# core.net
KiCad netlist of a schematic drawn in Altium Designer
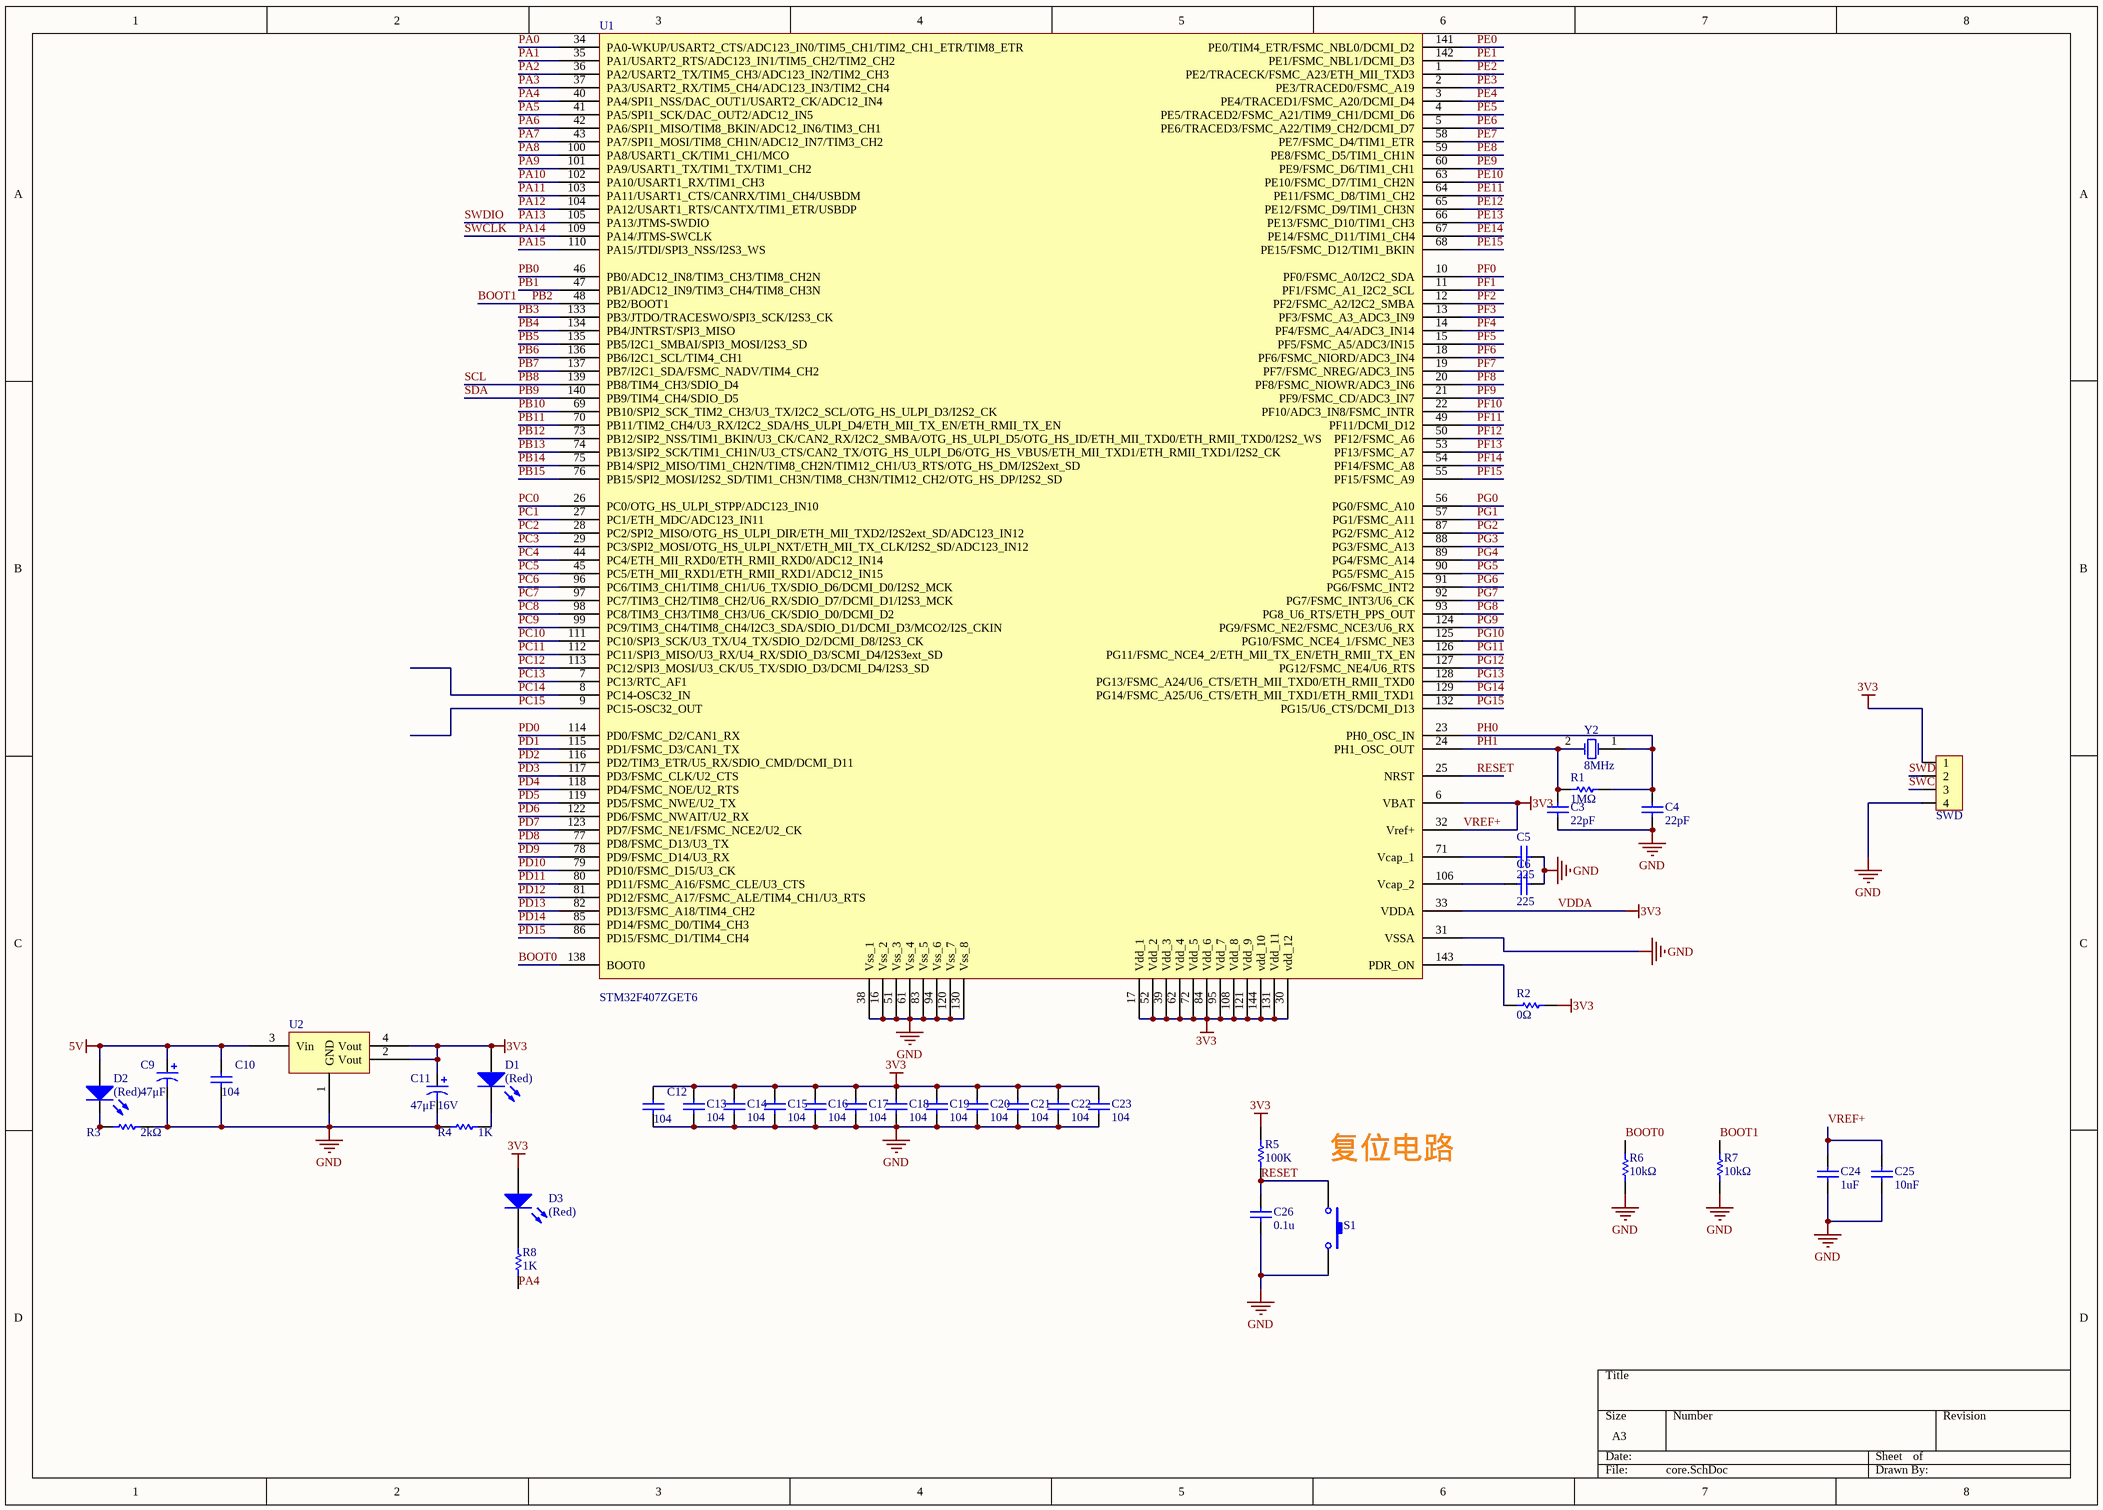
[diagram p0: core.SchDoc]

(export (version "E")
  (design (tool "Eeschema 10.0.6"))
  (components
    (comp (ref "C3")
      (value "22pF")
      (footprint "CAP-MLCC-0603")
      (description "无极性电容")
      (fields (field (name "Comment") "CAP") (field (name "PUBLISHER") "Altium Limited"))
      (libsource (lib "Libraries_2014_0215") (part "CAP"))
    )
    (comp (ref "C4")
      (value "22pF")
      (footprint "CAP-MLCC-0603")
      (description "无极性电容")
      (fields (field (name "Comment") "CAP") (field (name "PUBLISHER") "Altium Limited"))
      (libsource (lib "Libraries_2014_0215") (part "CAP"))
    )
    (comp (ref "C5")
      (value "225")
      (footprint "CAP-MLCC-0603")
      (description "无极性电容")
      (fields (field (name "PUBLISHER") "Altium Limited"))
      (libsource (lib "Libraries_2014_0618") (part "CAP"))
    )
    (comp (ref "C6")
      (value "225")
      (footprint "CAP-MLCC-0603")
      (description "无极性电容")
      (fields (field (name "PUBLISHER") "Altium Limited"))
      (libsource (lib "Libraries_2014_0618") (part "CAP"))
    )
    (comp (ref "C9")
      (value "47μF")
      (footprint "CAP-TAN-6032/CAPC")
      (description "钽电容")
      (fields (field (name "Comment") "CAP-TAN") (field (name "PUBLISHER") "Altium Limited"))
      (libsource (lib "Libraries_2014_0215") (part "CAP-TAN"))
    )
    (comp (ref "C10")
      (value "104")
      (footprint "CAP-MLCC-0603")
      (description "无极性电容")
      (fields (field (name "Comment") "CAP") (field (name "PUBLISHER") "Altium Limited"))
      (libsource (lib "Libraries_2014_0215") (part "CAP"))
    )
    (comp (ref "C11")
      (value "47μF")
      (footprint "CAP-TAN-6032/CAPC")
      (description "钽电容")
      (fields (field (name "Comment") "CAP-TAN") (field (name "PUBLISHER") "Altium Limited"))
      (libsource (lib "Libraries_2014_0215") (part "CAP-TAN"))
    )
    (comp (ref "C12")
      (value "104")
      (footprint "CAP-MLCC-0603")
      (description "无极性电容")
      (fields (field (name "Comment") "CAP") (field (name "PUBLISHER") "Altium Limited"))
      (libsource (lib "Libraries_2014_0215") (part "CAP"))
    )
    (comp (ref "C13")
      (value "104")
      (footprint "CAP-MLCC-0603")
      (description "无极性电容")
      (fields (field (name "Comment") "CAP") (field (name "PUBLISHER") "Altium Limited"))
      (libsource (lib "Libraries_2014_0215") (part "CAP"))
    )
    (comp (ref "C14")
      (value "104")
      (footprint "CAP-MLCC-0603")
      (description "无极性电容")
      (fields (field (name "Comment") "CAP") (field (name "PUBLISHER") "Altium Limited"))
      (libsource (lib "Libraries_2014_0215") (part "CAP"))
    )
    (comp (ref "C15")
      (value "104")
      (footprint "CAP-MLCC-0603")
      (description "无极性电容")
      (fields (field (name "Comment") "CAP") (field (name "PUBLISHER") "Altium Limited"))
      (libsource (lib "Libraries_2014_0215") (part "CAP"))
    )
    (comp (ref "C16")
      (value "104")
      (footprint "CAP-MLCC-0603")
      (description "无极性电容")
      (fields (field (name "Comment") "CAP") (field (name "PUBLISHER") "Altium Limited"))
      (libsource (lib "Libraries_2014_0215") (part "CAP"))
    )
    (comp (ref "C17")
      (value "104")
      (footprint "CAP-MLCC-0603")
      (description "无极性电容")
      (fields (field (name "Comment") "CAP") (field (name "PUBLISHER") "Altium Limited"))
      (libsource (lib "Libraries_2014_0215") (part "CAP"))
    )
    (comp (ref "C18")
      (value "104")
      (footprint "CAP-MLCC-0603")
      (description "无极性电容")
      (fields (field (name "Comment") "CAP") (field (name "PUBLISHER") "Altium Limited"))
      (libsource (lib "Libraries_2014_0215") (part "CAP"))
    )
    (comp (ref "C19")
      (value "104")
      (footprint "CAP-MLCC-0603")
      (description "无极性电容")
      (fields (field (name "Comment") "CAP") (field (name "PUBLISHER") "Altium Limited"))
      (libsource (lib "Libraries_2014_0215") (part "CAP"))
    )
    (comp (ref "C20")
      (value "104")
      (footprint "CAP-MLCC-0603")
      (description "无极性电容")
      (fields (field (name "Comment") "CAP") (field (name "PUBLISHER") "Altium Limited"))
      (libsource (lib "Libraries_2014_0215") (part "CAP"))
    )
    (comp (ref "C21")
      (value "104")
      (footprint "CAP-MLCC-0603")
      (description "无极性电容")
      (fields (field (name "Comment") "CAP") (field (name "PUBLISHER") "Altium Limited"))
      (libsource (lib "Libraries_2014_0215") (part "CAP"))
    )
    (comp (ref "C22")
      (value "104")
      (footprint "CAP-MLCC-0603")
      (description "无极性电容")
      (fields (field (name "Comment") "CAP") (field (name "PUBLISHER") "Altium Limited"))
      (libsource (lib "Libraries_2014_0215") (part "CAP"))
    )
    (comp (ref "C23")
      (value "104")
      (footprint "CAP-MLCC-0603")
      (description "无极性电容")
      (fields (field (name "Comment") "CAP") (field (name "PUBLISHER") "Altium Limited"))
      (libsource (lib "Libraries_2014_0215") (part "CAP"))
    )
    (comp (ref "C24")
      (value "1uF")
      (footprint "CAP-MLCC-0603")
      (description "无极性电容")
      (fields (field (name "PUBLISHER") "Altium Limited"))
      (libsource (lib "Libraries_2014_0618") (part "CAP"))
    )
    (comp (ref "C25")
      (value "10nF")
      (footprint "CAP-MLCC-0603")
      (description "无极性电容")
      (fields (field (name "PUBLISHER") "Altium Limited"))
      (libsource (lib "Libraries_2014_0618") (part "CAP"))
    )
    (comp (ref "C26")
      (value "0.1u")
      (footprint "CAP-MLCC-0603")
      (description "无极性电容")
      (fields (field (name "PUBLISHER") "Altium Limited"))
      (libsource (lib "Libraries_2014_0618") (part "CAP"))
    )
    (comp (ref "D1")
      (value "(Red)")
      (footprint "LED-1206")
      (description "LED")
      (fields (field (name "PUBLISHER") "Altium Limited"))
      (libsource (lib "Libraries_2014_0215") (part "LED"))
    )
    (comp (ref "D2")
      (value "(Red)")
      (footprint "LED-1206")
      (description "LED")
      (fields (field (name "PUBLISHER") "Altium Limited"))
      (libsource (lib "Libraries_2014_0215") (part "LED"))
    )
    (comp (ref "D3")
      (value "(Red)")
      (footprint "LED-1206")
      (description "LED")
      (fields (field (name "PUBLISHER") "Altium Limited"))
      (libsource (lib "Libraries_2014_0215") (part "LED"))
    )
    (comp (ref "R1")
      (value "1MΩ")
      (footprint "RES-0603")
      (description "电阻")
      (fields (field (name "PUBLISHER") "Altium Limited"))
      (libsource (lib "Libraries_2014_0618") (part "RES"))
    )
    (comp (ref "R2")
      (value "0Ω")
      (footprint "RES-0603")
      (description "电阻")
      (fields (field (name "PUBLISHER") "Altium Limited"))
      (libsource (lib "Libraries_2014_0618") (part "RES"))
    )
    (comp (ref "R3")
      (value "2kΩ")
      (footprint "RES-0603")
      (description "电阻")
      (fields (field (name "Comment") "RES") (field (name "PUBLISHER") "Altium Limited"))
      (libsource (lib "Libraries_2014_0215") (part "RES"))
    )
    (comp (ref "R4")
      (value "1K")
      (footprint "RES-0603")
      (description "电阻")
      (fields (field (name "Comment") "RES") (field (name "PUBLISHER") "Altium Limited"))
      (libsource (lib "Libraries_2014_0215") (part "RES"))
    )
    (comp (ref "R5")
      (value "100K")
      (footprint "RES-0603")
      (description "电阻")
      (fields (field (name "Comment") "RES") (field (name "PUBLISHER") "Altium Limited"))
      (libsource (lib "Libraries_2014_0215") (part "RES"))
    )
    (comp (ref "R6")
      (value "10kΩ")
      (footprint "RES-0603")
      (description "电阻")
      (fields (field (name "Comment") "RES") (field (name "PUBLISHER") "Altium Limited"))
      (libsource (lib "Libraries_2014_0215") (part "RES"))
    )
    (comp (ref "R7")
      (value "10kΩ")
      (footprint "RES-0603")
      (description "电阻")
      (fields (field (name "Comment") "RES") (field (name "PUBLISHER") "Altium Limited"))
      (libsource (lib "Libraries_2014_0215") (part "RES"))
    )
    (comp (ref "R8")
      (value "1K")
      (footprint "RES-0603")
      (description "电阻")
      (fields (field (name "Comment") "RES") (field (name "PUBLISHER") "Altium Limited"))
      (libsource (lib "Libraries_2014_0215") (part "RES"))
    )
    (comp (ref "S1")
      (value "SW-PB")
      (footprint "KEY_SMD")
      (description "Switch")
      (fields (field (name "PUBLISHER") "Altium Limited"))
      (libsource (lib "附加元件") (part "SW-PB"))
    )
    (comp (ref "SWD")
      (value "HDR1x4_2.54")
      (footprint "PCB_ConnectorHDR:HDR1x4_2.54_180")
      (description "Header")
      (libsource (lib "SCH_ConnectorHDR") (part "HDR1x4_2.54"))
    )
    (comp (ref "U1")
      (value "STM32F407ZGET6")
      (footprint "LQFP144-L")
      (libsource (lib "STM32F407VGT6") (part "Component_1"))
    )
    (comp (ref "U2")
      (value "IC-AS1117-3.3V")
      (footprint "SOT-223")
      (description "AS1117-3.3V")
      (libsource (lib "Libraries_2014_0215") (part "IC-AS1117-3.3V"))
    )
    (comp (ref "Y2")
      (value "8MHz")
      (footprint "XT_5032_2")
      (description "Crystal Oscillator")
      (fields (field (name "PUBLISHER") "Altium Limited"))
      (libsource (lib "Libraries_2014_0618") (part "C-Osc"))
    )
  )
  (nets
    (net (code "1") (name "/BOOT0") (class "Default")
      (node (ref "R6") (pin "2") (pinfunction "2_2") (pintype "passive"))
      (node (ref "U1") (pin "138") (pinfunction "BOOT0_138") (pintype "passive"))
    )
    (net (code "2") (name "/BOOT1") (class "Default")
      (node (ref "R7") (pin "2") (pinfunction "2_2") (pintype "passive"))
      (node (ref "U1") (pin "48") (pinfunction "PB2/BOOT1_48") (pintype "passive"))
    )
    (net (code "3") (name "/PA0") (class "Default")
      (node (ref "U1") (pin "34") (pinfunction "PA0-WKUP/USART2_CTS/ADC123_IN0/TIM5_CH1/TIM2_CH1_ETR/TIM8_ETR_34") (pintype "passive"))
    )
    (net (code "4") (name "/PA1") (class "Default")
      (node (ref "U1") (pin "35") (pinfunction "PA1/USART2_RTS/ADC123_IN1/TIM5_CH2/TIM2_CH2_35") (pintype "passive"))
    )
    (net (code "5") (name "/PA2") (class "Default")
      (node (ref "U1") (pin "36") (pinfunction "PA2/USART2_TX/TIM5_CH3/ADC123_IN2/TIM2_CH3_36") (pintype "passive"))
    )
    (net (code "6") (name "/PA3") (class "Default")
      (node (ref "U1") (pin "37") (pinfunction "PA3/USART2_RX/TIM5_CH4/ADC123_IN3/TIM2_CH4_37") (pintype "passive"))
    )
    (net (code "7") (name "/PA4") (class "Default")
      (node (ref "R8") (pin "1") (pinfunction "1_1") (pintype "passive"))
      (node (ref "U1") (pin "40") (pinfunction "PA4/SPI1_NSS/DAC_OUT1/USART2_CK/ADC12_IN4_40") (pintype "passive"))
    )
    (net (code "8") (name "/PA5") (class "Default")
      (node (ref "U1") (pin "41") (pinfunction "PA5/SPI1_SCK/DAC_OUT2/ADC12_IN5_41") (pintype "passive"))
    )
    (net (code "9") (name "/PA6") (class "Default")
      (node (ref "U1") (pin "42") (pinfunction "PA6/SPI1_MISO/TIM8_BKIN/ADC12_IN6/TIM3_CH1_42") (pintype "passive"))
    )
    (net (code "10") (name "/PA7") (class "Default")
      (node (ref "U1") (pin "43") (pinfunction "PA7/SPI1_MOSI/TIM8_CH1N/ADC12_IN7/TIM3_CH2_43") (pintype "passive"))
    )
    (net (code "11") (name "/PA8") (class "Default")
      (node (ref "U1") (pin "100") (pinfunction "PA8/USART1_CK/TIM1_CH1/MCO_100") (pintype "passive"))
    )
    (net (code "12") (name "/PA9") (class "Default")
      (node (ref "U1") (pin "101") (pinfunction "PA9/USART1_TX/TIM1_TX/TIM1_CH2_101") (pintype "passive"))
    )
    (net (code "13") (name "/PA10") (class "Default")
      (node (ref "U1") (pin "102") (pinfunction "PA10/USART1_RX/TIM1_CH3_102") (pintype "passive"))
    )
    (net (code "14") (name "/PA11") (class "Default")
      (node (ref "U1") (pin "103") (pinfunction "PA11/USART1_CTS/CANRX/TIM1_CH4/USBDM_103") (pintype "passive"))
    )
    (net (code "15") (name "/PA12") (class "Default")
      (node (ref "U1") (pin "104") (pinfunction "PA12/USART1_RTS/CANTX/TIM1_ETR/USBDP_104") (pintype "passive"))
    )
    (net (code "16") (name "/PA13") (class "Default")
      (node (ref "SWD") (pin "2") (pinfunction "2_2") (pintype "passive"))
      (node (ref "U1") (pin "105") (pinfunction "PA13/JTMS-SWDIO_105") (pintype "passive"))
    )
    (net (code "17") (name "/PA14") (class "Default")
      (node (ref "SWD") (pin "3") (pinfunction "3_3") (pintype "passive"))
      (node (ref "U1") (pin "109") (pinfunction "PA14/JTMS-SWCLK_109") (pintype "passive"))
    )
    (net (code "18") (name "/PA15") (class "Default")
      (node (ref "U1") (pin "110") (pinfunction "PA15/JTDI/SPI3_NSS/I2S3_WS_110") (pintype "passive"))
    )
    (net (code "19") (name "/PB0") (class "Default")
      (node (ref "U1") (pin "46") (pinfunction "PB0/ADC12_IN8/TIM3_CH3/TIM8_CH2N_46") (pintype "passive"))
    )
    (net (code "20") (name "/PB1") (class "Default")
      (node (ref "U1") (pin "47") (pinfunction "PB1/ADC12_IN9/TIM3_CH4/TIM8_CH3N_47") (pintype "passive"))
    )
    (net (code "21") (name "/PB3") (class "Default")
      (node (ref "U1") (pin "133") (pinfunction "PB3/JTDO/TRACESWO/SPI3_SCK/I2S3_CK_133") (pintype "passive"))
    )
    (net (code "22") (name "/PB4") (class "Default")
      (node (ref "U1") (pin "134") (pinfunction "PB4/JNTRST/SPI3_MISO_134") (pintype "passive"))
    )
    (net (code "23") (name "/PB5") (class "Default")
      (node (ref "U1") (pin "135") (pinfunction "PB5/I2C1_SMBAI/SPI3_MOSI/I2S3_SD_135") (pintype "passive"))
    )
    (net (code "24") (name "/PB6") (class "Default")
      (node (ref "U1") (pin "136") (pinfunction "PB6/I2C1_SCL/TIM4_CH1_136") (pintype "passive"))
    )
    (net (code "25") (name "/PB7") (class "Default")
      (node (ref "U1") (pin "137") (pinfunction "PB7/I2C1_SDA/FSMC_NADV/TIM4_CH2_137") (pintype "passive"))
    )
    (net (code "26") (name "/PB8") (class "Default")
      (node (ref "U1") (pin "139") (pinfunction "PB8/TIM4_CH3/SDIO_D4_139") (pintype "passive"))
    )
    (net (code "27") (name "/PB9") (class "Default")
      (node (ref "U1") (pin "140") (pinfunction "PB9/TIM4_CH4/SDIO_D5_140") (pintype "passive"))
    )
    (net (code "28") (name "/PB10") (class "Default")
      (node (ref "U1") (pin "69") (pinfunction "PB10/SPI2_SCK_TIM2_CH3/U3_TX/I2C2_SCL/OTG_HS_ULPI_D3/I2S2_CK_69") (pintype "passive"))
    )
    (net (code "29") (name "/PB11") (class "Default")
      (node (ref "U1") (pin "70") (pinfunction "PB11/TIM2_CH4/U3_RX/I2C2_SDA/HS_ULPI_D4/ETH_MII_TX_EN/ETH_RMII_TX_EN_70") (pintype "passive"))
    )
    (net (code "30") (name "/PB12") (class "Default")
      (node (ref "U1") (pin "73") (pinfunction "PB12/SIP2_NSS/TIM1_BKIN/U3_CK/CAN2_RX/I2C2_SMBA/OTG_HS_ULPI_D5/OTG_HS_ID/ETH_MII_TXD0/ETH_RMII_TXD0/I2S2_WS_73") (pintype "passive"))
    )
    (net (code "31") (name "/PB13") (class "Default")
      (node (ref "U1") (pin "74") (pinfunction "PB13/SIP2_SCK/TIM1_CH1N/U3_CTS/CAN2_TX/OTG_HS_ULPI_D6/OTG_HS_VBUS/ETH_MII_TXD1/ETH_RMII_TXD1/I2S2_CK_74") (pintype "passive"))
    )
    (net (code "32") (name "/PB14") (class "Default")
      (node (ref "U1") (pin "75") (pinfunction "PB14/SPI2_MISO/TIM1_CH2N/TIM8_CH2N/TIM12_CH1/U3_RTS/OTG_HS_DM/I2S2ext_SD_75") (pintype "passive"))
    )
    (net (code "33") (name "/PB15") (class "Default")
      (node (ref "U1") (pin "76") (pinfunction "PB15/SPI2_MOSI/I2S2_SD/TIM1_CH3N/TIM8_CH3N/TIM12_CH2/OTG_HS_DP/I2S2_SD_76") (pintype "passive"))
    )
    (net (code "34") (name "/PC0") (class "Default")
      (node (ref "U1") (pin "26") (pinfunction "PC0/OTG_HS_ULPI_STPP/ADC123_IN10_26") (pintype "passive"))
    )
    (net (code "35") (name "/PC1") (class "Default")
      (node (ref "U1") (pin "27") (pinfunction "PC1/ETH_MDC/ADC123_IN11_27") (pintype "passive"))
    )
    (net (code "36") (name "/PC2") (class "Default")
      (node (ref "U1") (pin "28") (pinfunction "PC2/SPI2_MISO/OTG_HS_ULPI_DIR/ETH_MII_TXD2/I2S2ext_SD/ADC123_IN12_28") (pintype "passive"))
    )
    (net (code "37") (name "/PC3") (class "Default")
      (node (ref "U1") (pin "29") (pinfunction "PC3/SPI2_MOSI/OTG_HS_ULPI_NXT/ETH_MII_TX_CLK/I2S2_SD/ADC123_IN12_29") (pintype "passive"))
    )
    (net (code "38") (name "/PC4") (class "Default")
      (node (ref "U1") (pin "44") (pinfunction "PC4/ETH_MII_RXD0/ETH_RMII_RXD0/ADC12_IN14_44") (pintype "passive"))
    )
    (net (code "39") (name "/PC5") (class "Default")
      (node (ref "U1") (pin "45") (pinfunction "PC5/ETH_MII_RXD1/ETH_RMII_RXD1/ADC12_IN15_45") (pintype "passive"))
    )
    (net (code "40") (name "/PC6") (class "Default")
      (node (ref "U1") (pin "96") (pinfunction "PC6/TIM3_CH1/TIM8_CH1/U6_TX/SDIO_D6/DCMI_D0/I2S2_MCK_96") (pintype "passive"))
    )
    (net (code "41") (name "/PC7") (class "Default")
      (node (ref "U1") (pin "97") (pinfunction "PC7/TIM3_CH2/TIM8_CH2/U6_RX/SDIO_D7/DCMI_D1/I2S3_MCK_97") (pintype "passive"))
    )
    (net (code "42") (name "/PC8") (class "Default")
      (node (ref "U1") (pin "98") (pinfunction "PC8/TIM3_CH3/TIM8_CH3/U6_CK/SDIO_D0/DCMI_D2_98") (pintype "passive"))
    )
    (net (code "43") (name "/PC9") (class "Default")
      (node (ref "U1") (pin "99") (pinfunction "PC9/TIM3_CH4/TIM8_CH4/I2C3_SDA/SDIO_D1/DCMI_D3/MCO2/I2S_CKIN_99") (pintype "passive"))
    )
    (net (code "44") (name "/PC10") (class "Default")
      (node (ref "U1") (pin "111") (pinfunction "PC10/SPI3_SCK/U3_TX/U4_TX/SDIO_D2/DCMI_D8/I2S3_CK_111") (pintype "passive"))
    )
    (net (code "45") (name "/PC11") (class "Default")
      (node (ref "U1") (pin "112") (pinfunction "PC11/SPI3_MISO/U3_RX/U4_RX/SDIO_D3/SCMI_D4/I2S3ext_SD_112") (pintype "passive"))
    )
    (net (code "46") (name "/PC12") (class "Default")
      (node (ref "U1") (pin "113") (pinfunction "PC12/SPI3_MOSI/U3_CK/U5_TX/SDIO_D3/DCMI_D4/I2S3_SD_113") (pintype "passive"))
    )
    (net (code "47") (name "/PC13") (class "Default")
      (node (ref "U1") (pin "7") (pinfunction "PC13/RTC_AF1_7") (pintype "passive"))
    )
    (net (code "48") (name "/PC14") (class "Default")
      (node (ref "U1") (pin "8") (pinfunction "PC14-OSC32_IN_8") (pintype "passive"))
    )
    (net (code "49") (name "/PC15") (class "Default")
      (node (ref "U1") (pin "9") (pinfunction "PC15-OSC32_OUT_9") (pintype "passive"))
    )
    (net (code "50") (name "/PD0") (class "Default")
      (node (ref "U1") (pin "114") (pinfunction "PD0/FSMC_D2/CAN1_RX_114") (pintype "passive"))
    )
    (net (code "51") (name "/PD1") (class "Default")
      (node (ref "U1") (pin "115") (pinfunction "PD1/FSMC_D3/CAN1_TX_115") (pintype "passive"))
    )
    (net (code "52") (name "/PD2") (class "Default")
      (node (ref "U1") (pin "116") (pinfunction "PD2/TIM3_ETR/U5_RX/SDIO_CMD/DCMI_D11_116") (pintype "passive"))
    )
    (net (code "53") (name "/PD3") (class "Default")
      (node (ref "U1") (pin "117") (pinfunction "PD3/FSMC_CLK/U2_CTS_117") (pintype "passive"))
    )
    (net (code "54") (name "/PD4") (class "Default")
      (node (ref "U1") (pin "118") (pinfunction "PD4/FSMC_NOE/U2_RTS_118") (pintype "passive"))
    )
    (net (code "55") (name "/PD5") (class "Default")
      (node (ref "U1") (pin "119") (pinfunction "PD5/FSMC_NWE/U2_TX_119") (pintype "passive"))
    )
    (net (code "56") (name "/PD6") (class "Default")
      (node (ref "U1") (pin "122") (pinfunction "PD6/FSMC_NWAIT/U2_RX_122") (pintype "passive"))
    )
    (net (code "57") (name "/PD7") (class "Default")
      (node (ref "U1") (pin "123") (pinfunction "PD7/FSMC_NE1/FSMC_NCE2/U2_CK_123") (pintype "passive"))
    )
    (net (code "58") (name "/PD8") (class "Default")
      (node (ref "U1") (pin "77") (pinfunction "PD8/FSMC_D13/U3_TX_77") (pintype "passive"))
    )
    (net (code "59") (name "/PD9") (class "Default")
      (node (ref "U1") (pin "78") (pinfunction "PD9/FSMC_D14/U3_RX_78") (pintype "passive"))
    )
    (net (code "60") (name "/PD10") (class "Default")
      (node (ref "U1") (pin "79") (pinfunction "PD10/FSMC_D15/U3_CK_79") (pintype "passive"))
    )
    (net (code "61") (name "/PD11") (class "Default")
      (node (ref "U1") (pin "80") (pinfunction "PD11/FSMC_A16/FSMC_CLE/U3_CTS_80") (pintype "passive"))
    )
    (net (code "62") (name "/PD12") (class "Default")
      (node (ref "U1") (pin "81") (pinfunction "PD12/FSMC_A17/FSMC_ALE/TIM4_CH1/U3_RTS_81") (pintype "passive"))
    )
    (net (code "63") (name "/PD13") (class "Default")
      (node (ref "U1") (pin "82") (pinfunction "PD13/FSMC_A18/TIM4_CH2_82") (pintype "passive"))
    )
    (net (code "64") (name "/PD14") (class "Default")
      (node (ref "U1") (pin "85") (pinfunction "PD14/FSMC_D0/TIM4_CH3_85") (pintype "passive"))
    )
    (net (code "65") (name "/PD15") (class "Default")
      (node (ref "U1") (pin "86") (pinfunction "PD15/FSMC_D1/TIM4_CH4_86") (pintype "passive"))
    )
    (net (code "66") (name "/PE0") (class "Default")
      (node (ref "U1") (pin "141") (pinfunction "PE0/TIM4_ETR/FSMC_NBL0/DCMI_D2_141") (pintype "passive"))
    )
    (net (code "67") (name "/PE1") (class "Default")
      (node (ref "U1") (pin "142") (pinfunction "PE1/FSMC_NBL1/DCMI_D3_142") (pintype "passive"))
    )
    (net (code "68") (name "/PE2") (class "Default")
      (node (ref "U1") (pin "1") (pinfunction "PE2/TRACECK/FSMC_A23/ETH_MII_TXD3_1") (pintype "passive"))
    )
    (net (code "69") (name "/PE3") (class "Default")
      (node (ref "U1") (pin "2") (pinfunction "PE3/TRACED0/FSMC_A19_2") (pintype "passive"))
    )
    (net (code "70") (name "/PE4") (class "Default")
      (node (ref "U1") (pin "3") (pinfunction "PE4/TRACED1/FSMC_A20/DCMI_D4_3") (pintype "passive"))
    )
    (net (code "71") (name "/PE5") (class "Default")
      (node (ref "U1") (pin "4") (pinfunction "PE5/TRACED2/FSMC_A21/TIM9_CH1/DCMI_D6_4") (pintype "passive"))
    )
    (net (code "72") (name "/PE6") (class "Default")
      (node (ref "U1") (pin "5") (pinfunction "PE6/TRACED3/FSMC_A22/TIM9_CH2/DCMI_D7_5") (pintype "passive"))
    )
    (net (code "73") (name "/PE7") (class "Default")
      (node (ref "U1") (pin "58") (pinfunction "PE7/FSMC_D4/TIM1_ETR_58") (pintype "passive"))
    )
    (net (code "74") (name "/PE8") (class "Default")
      (node (ref "U1") (pin "59") (pinfunction "PE8/FSMC_D5/TIM1_CH1N_59") (pintype "passive"))
    )
    (net (code "75") (name "/PE9") (class "Default")
      (node (ref "U1") (pin "60") (pinfunction "PE9/FSMC_D6/TIM1_CH1_60") (pintype "passive"))
    )
    (net (code "76") (name "/PE10") (class "Default")
      (node (ref "U1") (pin "63") (pinfunction "PE10/FSMC_D7/TIM1_CH2N_63") (pintype "passive"))
    )
    (net (code "77") (name "/PE11") (class "Default")
      (node (ref "U1") (pin "64") (pinfunction "PE11/FSMC_D8/TIM1_CH2_64") (pintype "passive"))
    )
    (net (code "78") (name "/PE12") (class "Default")
      (node (ref "U1") (pin "65") (pinfunction "PE12/FSMC_D9/TIM1_CH3N_65") (pintype "passive"))
    )
    (net (code "79") (name "/PE13") (class "Default")
      (node (ref "U1") (pin "66") (pinfunction "PE13/FSMC_D10/TIM1_CH3_66") (pintype "passive"))
    )
    (net (code "80") (name "/PE14") (class "Default")
      (node (ref "U1") (pin "67") (pinfunction "PE14/FSMC_D11/TIM1_CH4_67") (pintype "passive"))
    )
    (net (code "81") (name "/PE15") (class "Default")
      (node (ref "U1") (pin "68") (pinfunction "PE15/FSMC_D12/TIM1_BKIN_68") (pintype "passive"))
    )
    (net (code "82") (name "/PF0") (class "Default")
      (node (ref "U1") (pin "10") (pinfunction "PF0/FSMC_A0/I2C2_SDA_10") (pintype "passive"))
    )
    (net (code "83") (name "/PF1") (class "Default")
      (node (ref "U1") (pin "11") (pinfunction "PF1/FSMC_A1_I2C2_SCL_11") (pintype "passive"))
    )
    (net (code "84") (name "/PF2") (class "Default")
      (node (ref "U1") (pin "12") (pinfunction "PF2/FSMC_A2/I2C2_SMBA_12") (pintype "passive"))
    )
    (net (code "85") (name "/PF3") (class "Default")
      (node (ref "U1") (pin "13") (pinfunction "PF3/FSMC_A3_ADC3_IN9_13") (pintype "passive"))
    )
    (net (code "86") (name "/PF4") (class "Default")
      (node (ref "U1") (pin "14") (pinfunction "PF4/FSMC_A4/ADC3_IN14_14") (pintype "passive"))
    )
    (net (code "87") (name "/PF5") (class "Default")
      (node (ref "U1") (pin "15") (pinfunction "PF5/FSMC_A5/ADC3/IN15_15") (pintype "passive"))
    )
    (net (code "88") (name "/PF6") (class "Default")
      (node (ref "U1") (pin "18") (pinfunction "PF6/FSMC_NIORD/ADC3_IN4_18") (pintype "passive"))
    )
    (net (code "89") (name "/PF7") (class "Default")
      (node (ref "U1") (pin "19") (pinfunction "PF7/FSMC_NREG/ADC3_IN5_19") (pintype "passive"))
    )
    (net (code "90") (name "/PF8") (class "Default")
      (node (ref "U1") (pin "20") (pinfunction "PF8/FSMC_NIOWR/ADC3_IN6_20") (pintype "passive"))
    )
    (net (code "91") (name "/PF9") (class "Default")
      (node (ref "U1") (pin "21") (pinfunction "PF9/FSMC_CD/ADC3_IN7_21") (pintype "passive"))
    )
    (net (code "92") (name "/PF10") (class "Default")
      (node (ref "U1") (pin "22") (pinfunction "PF10/ADC3_IN8/FSMC_INTR_22") (pintype "passive"))
    )
    (net (code "93") (name "/PF11") (class "Default")
      (node (ref "U1") (pin "49") (pinfunction "PF11/DCMI_D12_49") (pintype "passive"))
    )
    (net (code "94") (name "/PF12") (class "Default")
      (node (ref "U1") (pin "50") (pinfunction "PF12/FSMC_A6_50") (pintype "passive"))
    )
    (net (code "95") (name "/PF13") (class "Default")
      (node (ref "U1") (pin "53") (pinfunction "PF13/FSMC_A7_53") (pintype "passive"))
    )
    (net (code "96") (name "/PF14") (class "Default")
      (node (ref "U1") (pin "54") (pinfunction "PF14/FSMC_A8_54") (pintype "passive"))
    )
    (net (code "97") (name "/PF15") (class "Default")
      (node (ref "U1") (pin "55") (pinfunction "PF15/FSMC_A9_55") (pintype "passive"))
    )
    (net (code "98") (name "/PG0") (class "Default")
      (node (ref "U1") (pin "56") (pinfunction "PG0/FSMC_A10_56") (pintype "passive"))
    )
    (net (code "99") (name "/PG1") (class "Default")
      (node (ref "U1") (pin "57") (pinfunction "PG1/FSMC_A11_57") (pintype "passive"))
    )
    (net (code "100") (name "/PG2") (class "Default")
      (node (ref "U1") (pin "87") (pinfunction "PG2/FSMC_A12_87") (pintype "passive"))
    )
    (net (code "101") (name "/PG3") (class "Default")
      (node (ref "U1") (pin "88") (pinfunction "PG3/FSMC_A13_88") (pintype "passive"))
    )
    (net (code "102") (name "/PG4") (class "Default")
      (node (ref "U1") (pin "89") (pinfunction "PG4/FSMC_A14_89") (pintype "passive"))
    )
    (net (code "103") (name "/PG5") (class "Default")
      (node (ref "U1") (pin "90") (pinfunction "PG5/FSMC_A15_90") (pintype "passive"))
    )
    (net (code "104") (name "/PG6") (class "Default")
      (node (ref "U1") (pin "91") (pinfunction "PG6/FSMC_INT2_91") (pintype "passive"))
    )
    (net (code "105") (name "/PG7") (class "Default")
      (node (ref "U1") (pin "92") (pinfunction "PG7/FSMC_INT3/U6_CK_92") (pintype "passive"))
    )
    (net (code "106") (name "/PG8") (class "Default")
      (node (ref "U1") (pin "93") (pinfunction "PG8_U6_RTS/ETH_PPS_OUT_93") (pintype "passive"))
    )
    (net (code "107") (name "/PG9") (class "Default")
      (node (ref "U1") (pin "124") (pinfunction "PG9/FSMC_NE2/FSMC_NCE3/U6_RX_124") (pintype "passive"))
    )
    (net (code "108") (name "/PG10") (class "Default")
      (node (ref "U1") (pin "125") (pinfunction "PG10/FSMC_NCE4_1/FSMC_NE3_125") (pintype "passive"))
    )
    (net (code "109") (name "/PG11") (class "Default")
      (node (ref "U1") (pin "126") (pinfunction "PG11/FSMC_NCE4_2/ETH_MII_TX_EN/ETH_RMII_TX_EN_126") (pintype "passive"))
    )
    (net (code "110") (name "/PG12") (class "Default")
      (node (ref "U1") (pin "127") (pinfunction "PG12/FSMC_NE4/U6_RTS_127") (pintype "passive"))
    )
    (net (code "111") (name "/PG13") (class "Default")
      (node (ref "U1") (pin "128") (pinfunction "PG13/FSMC_A24/U6_CTS/ETH_MII_TXD0/ETH_RMII_TXD0_128") (pintype "passive"))
    )
    (net (code "112") (name "/PG14") (class "Default")
      (node (ref "U1") (pin "129") (pinfunction "PG14/FSMC_A25/U6_CTS/ETH_MII_TXD1/ETH_RMII_TXD1_129") (pintype "passive"))
    )
    (net (code "113") (name "/PG15") (class "Default")
      (node (ref "U1") (pin "132") (pinfunction "PG15/U6_CTS/DCMI_D13_132") (pintype "passive"))
    )
    (net (code "114") (name "/PH0") (class "Default")
      (node (ref "C4") (pin "2") (pinfunction "2_2") (pintype "passive"))
      (node (ref "R1") (pin "2") (pinfunction "2_2") (pintype "passive"))
      (node (ref "U1") (pin "23") (pinfunction "PH0_OSC_IN_23") (pintype "passive"))
      (node (ref "Y2") (pin "1") (pinfunction "OSC1_1") (pintype "passive"))
    )
    (net (code "115") (name "/PH1") (class "Default")
      (node (ref "C3") (pin "2") (pinfunction "2_2") (pintype "passive"))
      (node (ref "R1") (pin "1") (pinfunction "1_1") (pintype "passive"))
      (node (ref "U1") (pin "24") (pinfunction "PH1_OSC_OUT_24") (pintype "passive"))
      (node (ref "Y2") (pin "2") (pinfunction "OSC2_2") (pintype "passive"))
    )
    (net (code "116") (name "/RESET") (class "Default")
      (node (ref "C26") (pin "2") (pinfunction "2_2") (pintype "passive"))
      (node (ref "R5") (pin "1") (pinfunction "1_1") (pintype "passive"))
      (node (ref "S1") (pin "1") (pinfunction "1_1") (pintype "passive"))
      (node (ref "U1") (pin "25") (pinfunction "NRST_25") (pintype "passive"))
    )
    (net (code "117") (name "3V3") (class "Default")
      (node (ref "C11") (pin "1") (pinfunction "1_1") (pintype "passive"))
      (node (ref "C12") (pin "2") (pinfunction "2_2") (pintype "passive"))
      (node (ref "C13") (pin "2") (pinfunction "2_2") (pintype "passive"))
      (node (ref "C14") (pin "2") (pinfunction "2_2") (pintype "passive"))
      (node (ref "C15") (pin "2") (pinfunction "2_2") (pintype "passive"))
      (node (ref "C16") (pin "2") (pinfunction "2_2") (pintype "passive"))
      (node (ref "C17") (pin "2") (pinfunction "2_2") (pintype "passive"))
      (node (ref "C18") (pin "2") (pinfunction "2_2") (pintype "passive"))
      (node (ref "C19") (pin "2") (pinfunction "2_2") (pintype "passive"))
      (node (ref "C20") (pin "2") (pinfunction "2_2") (pintype "passive"))
      (node (ref "C21") (pin "2") (pinfunction "2_2") (pintype "passive"))
      (node (ref "C22") (pin "2") (pinfunction "2_2") (pintype "passive"))
      (node (ref "C23") (pin "2") (pinfunction "2_2") (pintype "passive"))
      (node (ref "C24") (pin "2") (pinfunction "2_2") (pintype "passive"))
      (node (ref "C25") (pin "2") (pinfunction "2_2") (pintype "passive"))
      (node (ref "D1") (pin "1") (pinfunction "A_1") (pintype "passive"))
      (node (ref "D3") (pin "1") (pinfunction "A_1") (pintype "passive"))
      (node (ref "R2") (pin "1") (pinfunction "1_1") (pintype "passive"))
      (node (ref "R5") (pin "2") (pinfunction "2_2") (pintype "passive"))
      (node (ref "SWD") (pin "1") (pinfunction "1_1") (pintype "passive"))
      (node (ref "U1") (pin "108") (pinfunction "Vdd_8_108") (pintype "passive"))
      (node (ref "U1") (pin "121") (pinfunction "Vdd_9_121") (pintype "passive"))
      (node (ref "U1") (pin "131") (pinfunction "Vdd_11_131") (pintype "passive"))
      (node (ref "U1") (pin "144") (pinfunction "vdd_10_144") (pintype "passive"))
      (node (ref "U1") (pin "17") (pinfunction "Vdd_1_17") (pintype "passive"))
      (node (ref "U1") (pin "30") (pinfunction "vdd_12_30") (pintype "passive"))
      (node (ref "U1") (pin "32") (pinfunction "Vref+_32") (pintype "passive"))
      (node (ref "U1") (pin "33") (pinfunction "VDDA_33") (pintype "passive"))
      (node (ref "U1") (pin "39") (pinfunction "Vdd_3_39") (pintype "passive"))
      (node (ref "U1") (pin "52") (pinfunction "Vdd_2_52") (pintype "passive"))
      (node (ref "U1") (pin "6") (pinfunction "VBAT_6") (pintype "passive"))
      (node (ref "U1") (pin "62") (pinfunction "Vdd_4_62") (pintype "passive"))
      (node (ref "U1") (pin "72") (pinfunction "Vdd_5_72") (pintype "passive"))
      (node (ref "U1") (pin "84") (pinfunction "Vdd_6_84") (pintype "passive"))
      (node (ref "U1") (pin "95") (pinfunction "Vdd_7_95") (pintype "passive"))
      (node (ref "U2") (pin "2") (pinfunction "Vout_2") (pintype "power_in"))
      (node (ref "U2") (pin "4") (pinfunction "Vout_4") (pintype "power_in"))
    )
    (net (code "118") (name "5V") (class "Default")
      (node (ref "C10") (pin "2") (pinfunction "2_2") (pintype "passive"))
      (node (ref "C9") (pin "1") (pinfunction "1_1") (pintype "passive"))
      (node (ref "D2") (pin "1") (pinfunction "A_1") (pintype "passive"))
      (node (ref "U2") (pin "3") (pinfunction "Vin_3") (pintype "power_in"))
    )
    (net (code "119") (name "GND") (class "Default")
      (node (ref "C10") (pin "1") (pinfunction "1_1") (pintype "passive"))
      (node (ref "C11") (pin "2") (pinfunction "2_2") (pintype "passive"))
      (node (ref "C12") (pin "1") (pinfunction "1_1") (pintype "passive"))
      (node (ref "C13") (pin "1") (pinfunction "1_1") (pintype "passive"))
      (node (ref "C14") (pin "1") (pinfunction "1_1") (pintype "passive"))
      (node (ref "C15") (pin "1") (pinfunction "1_1") (pintype "passive"))
      (node (ref "C16") (pin "1") (pinfunction "1_1") (pintype "passive"))
      (node (ref "C17") (pin "1") (pinfunction "1_1") (pintype "passive"))
      (node (ref "C18") (pin "1") (pinfunction "1_1") (pintype "passive"))
      (node (ref "C19") (pin "1") (pinfunction "1_1") (pintype "passive"))
      (node (ref "C20") (pin "1") (pinfunction "1_1") (pintype "passive"))
      (node (ref "C21") (pin "1") (pinfunction "1_1") (pintype "passive"))
      (node (ref "C22") (pin "1") (pinfunction "1_1") (pintype "passive"))
      (node (ref "C23") (pin "1") (pinfunction "1_1") (pintype "passive"))
      (node (ref "C24") (pin "1") (pinfunction "1_1") (pintype "passive"))
      (node (ref "C25") (pin "1") (pinfunction "1_1") (pintype "passive"))
      (node (ref "C26") (pin "1") (pinfunction "1_1") (pintype "passive"))
      (node (ref "C3") (pin "1") (pinfunction "1_1") (pintype "passive"))
      (node (ref "C4") (pin "1") (pinfunction "1_1") (pintype "passive"))
      (node (ref "C5") (pin "2") (pinfunction "2_2") (pintype "passive"))
      (node (ref "C6") (pin "2") (pinfunction "2_2") (pintype "passive"))
      (node (ref "C9") (pin "2") (pinfunction "2_2") (pintype "passive"))
      (node (ref "R3") (pin "2") (pinfunction "2_2") (pintype "passive"))
      (node (ref "R4") (pin "1") (pinfunction "1_1") (pintype "passive"))
      (node (ref "R6") (pin "1") (pinfunction "1_1") (pintype "passive"))
      (node (ref "R7") (pin "1") (pinfunction "1_1") (pintype "passive"))
      (node (ref "S1") (pin "2") (pinfunction "2_2") (pintype "passive"))
      (node (ref "SWD") (pin "4") (pinfunction "4_4") (pintype "passive"))
      (node (ref "U1") (pin "120") (pinfunction "Vss_7_120") (pintype "passive"))
      (node (ref "U1") (pin "130") (pinfunction "Vss_8_130") (pintype "passive"))
      (node (ref "U1") (pin "16") (pinfunction "Vss_2_16") (pintype "passive"))
      (node (ref "U1") (pin "31") (pinfunction "VSSA_31") (pintype "passive"))
      (node (ref "U1") (pin "38") (pinfunction "Vss_1_38") (pintype "passive"))
      (node (ref "U1") (pin "51") (pinfunction "Vss_3_51") (pintype "passive"))
      (node (ref "U1") (pin "61") (pinfunction "Vss_4_61") (pintype "passive"))
      (node (ref "U1") (pin "83") (pinfunction "Vss_5_83") (pintype "passive"))
      (node (ref "U1") (pin "94") (pinfunction "Vss_6_94") (pintype "passive"))
      (node (ref "U2") (pin "1") (pinfunction "GND_1") (pintype "power_in"))
    )
    (net (code "120") (name "Net-(D1-K)") (class "Default")
      (node (ref "D1") (pin "2") (pinfunction "K_2") (pintype "passive"))
      (node (ref "R4") (pin "2") (pinfunction "2_2") (pintype "passive"))
    )
    (net (code "121") (name "Net-(D2-K)") (class "Default")
      (node (ref "D2") (pin "2") (pinfunction "K_2") (pintype "passive"))
      (node (ref "R3") (pin "1") (pinfunction "1_1") (pintype "passive"))
    )
    (net (code "122") (name "Net-(D3-K)") (class "Default")
      (node (ref "D3") (pin "2") (pinfunction "K_2") (pintype "passive"))
      (node (ref "R8") (pin "2") (pinfunction "2_2") (pintype "passive"))
    )
    (net (code "123") (name "Net-(U1-PDR_ON)") (class "Default")
      (node (ref "R2") (pin "2") (pinfunction "2_2") (pintype "passive"))
      (node (ref "U1") (pin "143") (pinfunction "PDR_ON_143") (pintype "passive"))
    )
    (net (code "124") (name "Net-(U1-Vcap_1)") (class "Default")
      (node (ref "C5") (pin "1") (pinfunction "1_1") (pintype "passive"))
      (node (ref "U1") (pin "71") (pinfunction "Vcap_1_71") (pintype "passive"))
    )
    (net (code "125") (name "Net-(U1-Vcap_2)") (class "Default")
      (node (ref "C6") (pin "1") (pinfunction "1_1") (pintype "passive"))
      (node (ref "U1") (pin "106") (pinfunction "Vcap_2_106") (pintype "passive"))
    )
  )
)
